# LED.net
KiCad netlist of a schematic drawn in Altium Designer
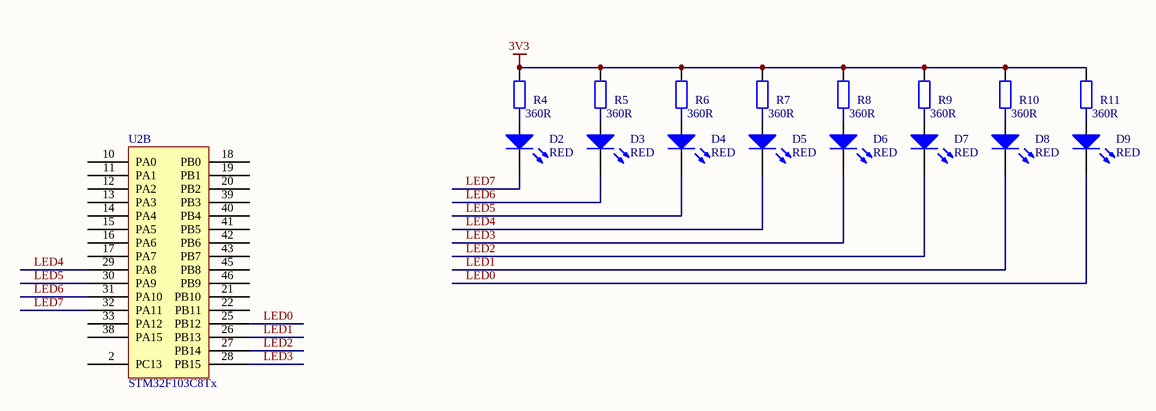
[diagram p0: LED.SchDoc]

(export (version "E")
  (design (tool "Eeschema 10.0.6"))
  (components
    (comp (ref "D2")
      (value "RED")
      (footprint "MicroControl:LED0603-RED")
      (description "Typical INFRARED GaAs LED")
      (fields (field (name "PUBLISHER") "Altium Limited"))
      (libsource (lib "Miscellaneous Devices") (part "LED0"))
    )
    (comp (ref "D3")
      (value "RED")
      (footprint "MicroControl:LED0603-RED")
      (description "Typical INFRARED GaAs LED")
      (fields (field (name "PUBLISHER") "Altium Limited"))
      (libsource (lib "Miscellaneous Devices") (part "LED0"))
    )
    (comp (ref "D4")
      (value "RED")
      (footprint "MicroControl:LED0603-RED")
      (description "Typical INFRARED GaAs LED")
      (fields (field (name "PUBLISHER") "Altium Limited"))
      (libsource (lib "Miscellaneous Devices") (part "LED0"))
    )
    (comp (ref "D5")
      (value "RED")
      (footprint "MicroControl:LED0603-RED")
      (description "Typical INFRARED GaAs LED")
      (fields (field (name "PUBLISHER") "Altium Limited"))
      (libsource (lib "Miscellaneous Devices") (part "LED0"))
    )
    (comp (ref "D6")
      (value "RED")
      (footprint "MicroControl:LED0603-RED")
      (description "Typical INFRARED GaAs LED")
      (fields (field (name "PUBLISHER") "Altium Limited"))
      (libsource (lib "Miscellaneous Devices") (part "LED0"))
    )
    (comp (ref "D7")
      (value "RED")
      (footprint "MicroControl:LED0603-RED")
      (description "Typical INFRARED GaAs LED")
      (fields (field (name "PUBLISHER") "Altium Limited"))
      (libsource (lib "Miscellaneous Devices") (part "LED0"))
    )
    (comp (ref "D8")
      (value "RED")
      (footprint "MicroControl:LED0603-RED")
      (description "Typical INFRARED GaAs LED")
      (fields (field (name "PUBLISHER") "Altium Limited"))
      (libsource (lib "Miscellaneous Devices") (part "LED0"))
    )
    (comp (ref "D9")
      (value "RED")
      (footprint "MicroControl:LED0603-RED")
      (description "Typical INFRARED GaAs LED")
      (fields (field (name "PUBLISHER") "Altium Limited"))
      (libsource (lib "Miscellaneous Devices") (part "LED0"))
    )
    (comp (ref "R4")
      (value "360R")
      (footprint "MicroControl:R0603")
      (description "Resistor")
      (fields (field (name "PUBLISHER") "Altium Limited"))
      (libsource (lib "Miscellaneous Devices") (part "Res2"))
    )
    (comp (ref "R5")
      (value "360R")
      (footprint "MicroControl:R0603")
      (description "Resistor")
      (fields (field (name "PUBLISHER") "Altium Limited"))
      (libsource (lib "Miscellaneous Devices") (part "Res2"))
    )
    (comp (ref "R6")
      (value "360R")
      (footprint "MicroControl:R0603")
      (description "Resistor")
      (fields (field (name "PUBLISHER") "Altium Limited"))
      (libsource (lib "Miscellaneous Devices") (part "Res2"))
    )
    (comp (ref "R7")
      (value "360R")
      (footprint "MicroControl:R0603")
      (description "Resistor")
      (fields (field (name "PUBLISHER") "Altium Limited"))
      (libsource (lib "Miscellaneous Devices") (part "Res2"))
    )
    (comp (ref "R8")
      (value "360R")
      (footprint "MicroControl:R0603")
      (description "Resistor")
      (fields (field (name "PUBLISHER") "Altium Limited"))
      (libsource (lib "Miscellaneous Devices") (part "Res2"))
    )
    (comp (ref "R9")
      (value "360R")
      (footprint "MicroControl:R0603")
      (description "Resistor")
      (fields (field (name "PUBLISHER") "Altium Limited"))
      (libsource (lib "Miscellaneous Devices") (part "Res2"))
    )
    (comp (ref "R10")
      (value "360R")
      (footprint "MicroControl:R0603")
      (description "Resistor")
      (fields (field (name "PUBLISHER") "Altium Limited"))
      (libsource (lib "Miscellaneous Devices") (part "Res2"))
    )
    (comp (ref "R11")
      (value "360R")
      (footprint "MicroControl:R0603")
      (description "Resistor")
      (fields (field (name "PUBLISHER") "Altium Limited"))
      (libsource (lib "Miscellaneous Devices") (part "Res2"))
    )
    (comp (ref "U2")
      (value "STM32F103C8Tx")
      (footprint "Integrated_Circuit:PQFP48")
      (libsource (lib "yinhaonanLib") (part "STM32F103C8Tx"))
    )
  )
  (nets
    (net (code "1") (name "/LED0") (class "Default")
      (node (ref "D9") (pin "2") (pinfunction "K_2") (pintype "passive"))
      (node (ref "U2") (pin "25") (pinfunction "PB12_25") (pintype "passive"))
    )
    (net (code "2") (name "/LED1") (class "Default")
      (node (ref "D8") (pin "2") (pinfunction "K_2") (pintype "passive"))
      (node (ref "U2") (pin "26") (pinfunction "PB13_26") (pintype "passive"))
    )
    (net (code "3") (name "/LED2") (class "Default")
      (node (ref "D7") (pin "2") (pinfunction "K_2") (pintype "passive"))
      (node (ref "U2") (pin "27") (pinfunction "PB14_27") (pintype "passive"))
    )
    (net (code "4") (name "/LED3") (class "Default")
      (node (ref "D6") (pin "2") (pinfunction "K_2") (pintype "passive"))
      (node (ref "U2") (pin "28") (pinfunction "PB15_28") (pintype "passive"))
    )
    (net (code "5") (name "/LED4") (class "Default")
      (node (ref "D5") (pin "2") (pinfunction "K_2") (pintype "passive"))
      (node (ref "U2") (pin "29") (pinfunction "PA8_29") (pintype "passive"))
    )
    (net (code "6") (name "/LED5") (class "Default")
      (node (ref "D4") (pin "2") (pinfunction "K_2") (pintype "passive"))
      (node (ref "U2") (pin "30") (pinfunction "PA9_30") (pintype "passive"))
    )
    (net (code "7") (name "/LED6") (class "Default")
      (node (ref "D3") (pin "2") (pinfunction "K_2") (pintype "passive"))
      (node (ref "U2") (pin "31") (pinfunction "PA10_31") (pintype "passive"))
    )
    (net (code "8") (name "/LED7") (class "Default")
      (node (ref "D2") (pin "2") (pinfunction "K_2") (pintype "passive"))
      (node (ref "U2") (pin "32") (pinfunction "PA11_32") (pintype "passive"))
    )
    (net (code "9") (name "3V3") (class "Default")
      (node (ref "R10") (pin "1") (pinfunction "1_1") (pintype "passive"))
      (node (ref "R11") (pin "1") (pinfunction "1_1") (pintype "passive"))
      (node (ref "R4") (pin "1") (pinfunction "1_1") (pintype "passive"))
      (node (ref "R5") (pin "1") (pinfunction "1_1") (pintype "passive"))
      (node (ref "R6") (pin "1") (pinfunction "1_1") (pintype "passive"))
      (node (ref "R7") (pin "1") (pinfunction "1_1") (pintype "passive"))
      (node (ref "R8") (pin "1") (pinfunction "1_1") (pintype "passive"))
      (node (ref "R9") (pin "1") (pinfunction "1_1") (pintype "passive"))
    )
    (net (code "10") (name "Net-(D2-A)") (class "Default")
      (node (ref "D2") (pin "1") (pinfunction "A_1") (pintype "passive"))
      (node (ref "R4") (pin "2") (pinfunction "2_2") (pintype "passive"))
    )
    (net (code "11") (name "Net-(D3-A)") (class "Default")
      (node (ref "D3") (pin "1") (pinfunction "A_1") (pintype "passive"))
      (node (ref "R5") (pin "2") (pinfunction "2_2") (pintype "passive"))
    )
    (net (code "12") (name "Net-(D4-A)") (class "Default")
      (node (ref "D4") (pin "1") (pinfunction "A_1") (pintype "passive"))
      (node (ref "R6") (pin "2") (pinfunction "2_2") (pintype "passive"))
    )
    (net (code "13") (name "Net-(D5-A)") (class "Default")
      (node (ref "D5") (pin "1") (pinfunction "A_1") (pintype "passive"))
      (node (ref "R7") (pin "2") (pinfunction "2_2") (pintype "passive"))
    )
    (net (code "14") (name "Net-(D6-A)") (class "Default")
      (node (ref "D6") (pin "1") (pinfunction "A_1") (pintype "passive"))
      (node (ref "R8") (pin "2") (pinfunction "2_2") (pintype "passive"))
    )
    (net (code "15") (name "Net-(D7-A)") (class "Default")
      (node (ref "D7") (pin "1") (pinfunction "A_1") (pintype "passive"))
      (node (ref "R9") (pin "2") (pinfunction "2_2") (pintype "passive"))
    )
    (net (code "16") (name "Net-(D8-A)") (class "Default")
      (node (ref "D8") (pin "1") (pinfunction "A_1") (pintype "passive"))
      (node (ref "R10") (pin "2") (pinfunction "2_2") (pintype "passive"))
    )
    (net (code "17") (name "Net-(D9-A)") (class "Default")
      (node (ref "D9") (pin "1") (pinfunction "A_1") (pintype "passive"))
      (node (ref "R11") (pin "2") (pinfunction "2_2") (pintype "passive"))
    )
    (net (code "18") (name "unconnected-(U2B-PA0-Pad10)") (class "Default")
      (node (ref "U2") (pin "10") (pinfunction "PA0_10") (pintype "passive"))
    )
    (net (code "19") (name "unconnected-(U2B-PA1-Pad11)") (class "Default")
      (node (ref "U2") (pin "11") (pinfunction "PA1_11") (pintype "passive"))
    )
    (net (code "20") (name "unconnected-(U2B-PA2-Pad12)") (class "Default")
      (node (ref "U2") (pin "12") (pinfunction "PA2_12") (pintype "passive"))
    )
    (net (code "21") (name "unconnected-(U2B-PA3-Pad13)") (class "Default")
      (node (ref "U2") (pin "13") (pinfunction "PA3_13") (pintype "passive"))
    )
    (net (code "22") (name "unconnected-(U2B-PA4-Pad14)") (class "Default")
      (node (ref "U2") (pin "14") (pinfunction "PA4_14") (pintype "passive"))
    )
    (net (code "23") (name "unconnected-(U2B-PA5-Pad15)") (class "Default")
      (node (ref "U2") (pin "15") (pinfunction "PA5_15") (pintype "passive"))
    )
    (net (code "24") (name "unconnected-(U2B-PA6-Pad16)") (class "Default")
      (node (ref "U2") (pin "16") (pinfunction "PA6_16") (pintype "passive"))
    )
    (net (code "25") (name "unconnected-(U2B-PA7-Pad17)") (class "Default")
      (node (ref "U2") (pin "17") (pinfunction "PA7_17") (pintype "passive"))
    )
    (net (code "26") (name "unconnected-(U2B-PA12-Pad33)") (class "Default")
      (node (ref "U2") (pin "33") (pinfunction "PA12_33") (pintype "passive"))
    )
    (net (code "27") (name "unconnected-(U2B-PA15-Pad38)") (class "Default")
      (node (ref "U2") (pin "38") (pinfunction "PA15_38") (pintype "passive"))
    )
    (net (code "28") (name "unconnected-(U2B-PB0-Pad18)") (class "Default")
      (node (ref "U2") (pin "18") (pinfunction "PB0_18") (pintype "passive"))
    )
    (net (code "29") (name "unconnected-(U2B-PB1-Pad19)") (class "Default")
      (node (ref "U2") (pin "19") (pinfunction "PB1_19") (pintype "passive"))
    )
    (net (code "30") (name "unconnected-(U2B-PB2-Pad20)") (class "Default")
      (node (ref "U2") (pin "20") (pinfunction "PB2_20") (pintype "passive"))
    )
    (net (code "31") (name "unconnected-(U2B-PB3-Pad39)") (class "Default")
      (node (ref "U2") (pin "39") (pinfunction "PB3_39") (pintype "passive"))
    )
    (net (code "32") (name "unconnected-(U2B-PB4-Pad40)") (class "Default")
      (node (ref "U2") (pin "40") (pinfunction "PB4_40") (pintype "passive"))
    )
    (net (code "33") (name "unconnected-(U2B-PB5-Pad41)") (class "Default")
      (node (ref "U2") (pin "41") (pinfunction "PB5_41") (pintype "passive"))
    )
    (net (code "34") (name "unconnected-(U2B-PB6-Pad42)") (class "Default")
      (node (ref "U2") (pin "42") (pinfunction "PB6_42") (pintype "passive"))
    )
    (net (code "35") (name "unconnected-(U2B-PB7-Pad43)") (class "Default")
      (node (ref "U2") (pin "43") (pinfunction "PB7_43") (pintype "passive"))
    )
    (net (code "36") (name "unconnected-(U2B-PB8-Pad45)") (class "Default")
      (node (ref "U2") (pin "45") (pinfunction "PB8_45") (pintype "passive"))
    )
    (net (code "37") (name "unconnected-(U2B-PB9-Pad46)") (class "Default")
      (node (ref "U2") (pin "46") (pinfunction "PB9_46") (pintype "passive"))
    )
    (net (code "38") (name "unconnected-(U2B-PB10-Pad21)") (class "Default")
      (node (ref "U2") (pin "21") (pinfunction "PB10_21") (pintype "passive"))
    )
    (net (code "39") (name "unconnected-(U2B-PB11-Pad22)") (class "Default")
      (node (ref "U2") (pin "22") (pinfunction "PB11_22") (pintype "passive"))
    )
    (net (code "40") (name "unconnected-(U2B-PC13-Pad2)") (class "Default")
      (node (ref "U2") (pin "2") (pinfunction "PC13_2") (pintype "passive"))
    )
  )
)
